# HydroController2016.net
KiCad netlist of a schematic drawn in Altium Designer
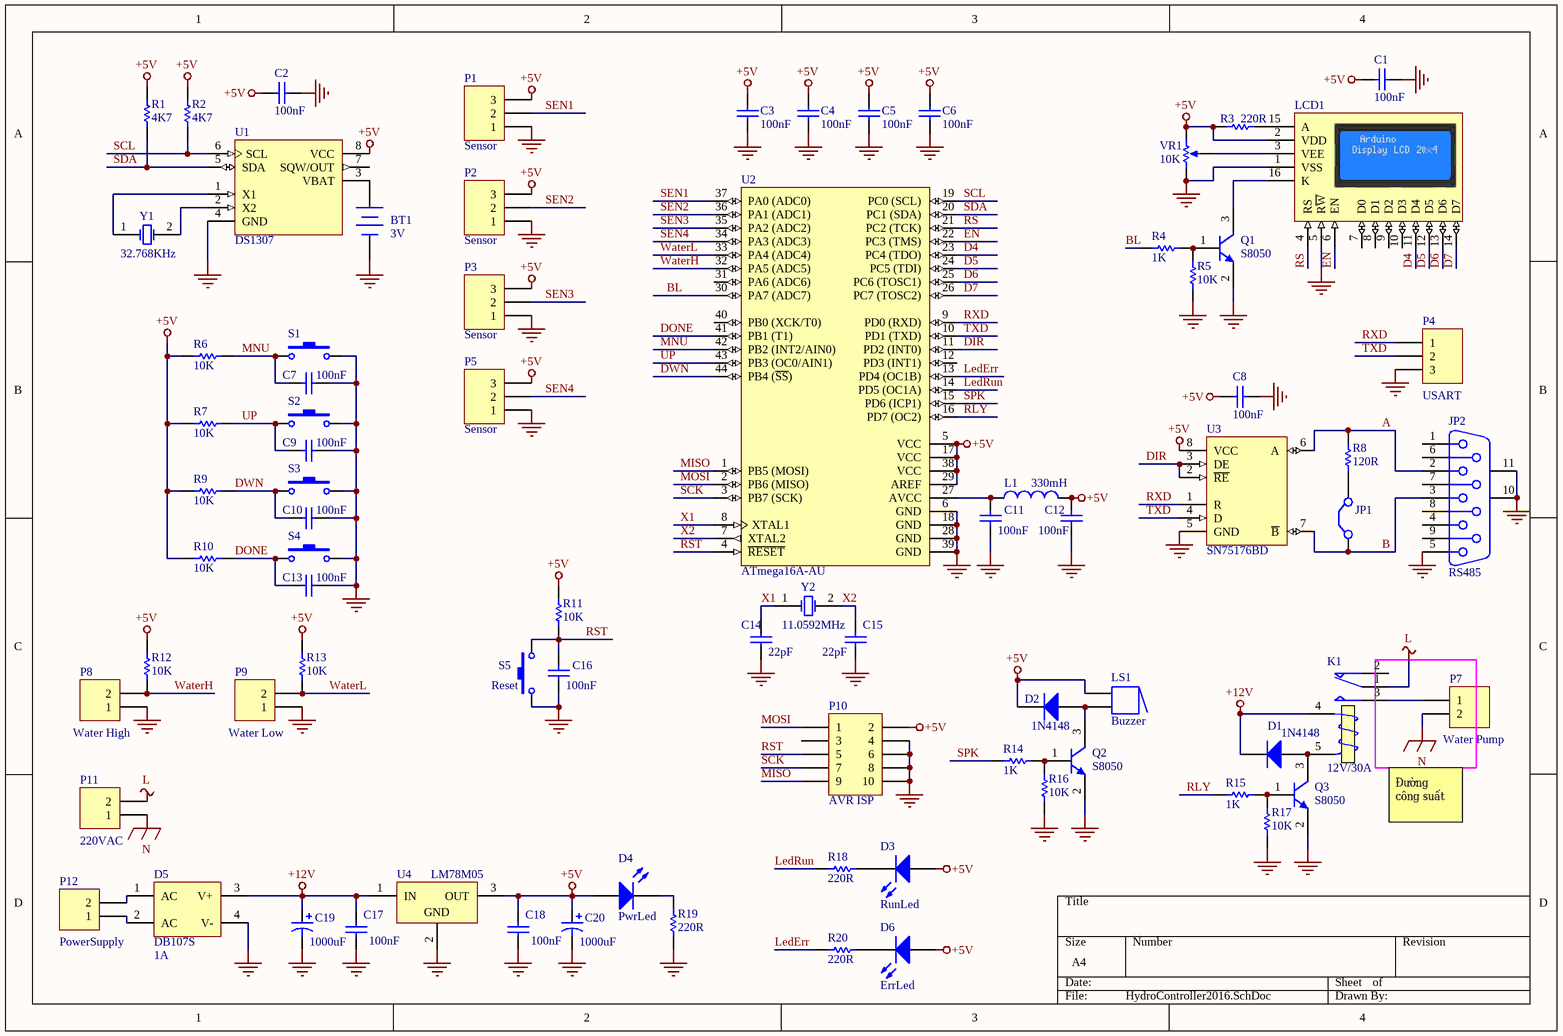
[diagram p0: HydroController2016.SchDoc]

(export (version "E")
  (design (tool "Eeschema 10.0.6"))
  (components
    (comp (ref "BT1")
      (value "3V")
      (footprint "SK-BATT-CR1220")
      (description "Multicell Battery")
      (libsource (lib "Miscellaneous Devices") (part "Battery"))
    )
    (comp (ref "C1")
      (value "100nF")
      (footprint "C-0805")
      (description "Capacitor")
      (fields (field (name "Comment") "104") (field (name "PUBLISHER") "Altium Limited"))
      (libsource (lib "Miscellaneous Devices") (part "Cap"))
    )
    (comp (ref "C2")
      (value "100nF")
      (footprint "C-0805")
      (description "Capacitor")
      (fields (field (name "Comment") "104") (field (name "PUBLISHER") "Altium Limited"))
      (libsource (lib "Miscellaneous Devices") (part "Cap"))
    )
    (comp (ref "C3")
      (value "100nF")
      (footprint "C-0805")
      (description "Capacitor")
      (fields (field (name "Comment") "104") (field (name "PUBLISHER") "Altium Limited"))
      (libsource (lib "Miscellaneous Devices") (part "Cap"))
    )
    (comp (ref "C4")
      (value "100nF")
      (footprint "C-0805")
      (description "Capacitor")
      (fields (field (name "Comment") "104") (field (name "PUBLISHER") "Altium Limited"))
      (libsource (lib "Miscellaneous Devices") (part "Cap"))
    )
    (comp (ref "C5")
      (value "100nF")
      (footprint "C-0805")
      (description "Capacitor")
      (fields (field (name "Comment") "104") (field (name "PUBLISHER") "Altium Limited"))
      (libsource (lib "Miscellaneous Devices") (part "Cap"))
    )
    (comp (ref "C6")
      (value "100nF")
      (footprint "C-0805")
      (description "Capacitor")
      (fields (field (name "Comment") "104") (field (name "PUBLISHER") "Altium Limited"))
      (libsource (lib "Miscellaneous Devices") (part "Cap"))
    )
    (comp (ref "C7")
      (value "100nF")
      (footprint "C-0805")
      (description "Capacitor")
      (fields (field (name "Comment") "104") (field (name "PUBLISHER") "Altium Limited"))
      (libsource (lib "Miscellaneous Devices") (part "Cap"))
    )
    (comp (ref "C8")
      (value "100nF")
      (footprint "C-0805")
      (description "Capacitor")
      (fields (field (name "Comment") "104") (field (name "PUBLISHER") "Altium Limited"))
      (libsource (lib "Miscellaneous Devices") (part "Cap"))
    )
    (comp (ref "C9")
      (value "100nF")
      (footprint "C-0805")
      (description "Capacitor")
      (fields (field (name "Comment") "104") (field (name "PUBLISHER") "Altium Limited"))
      (libsource (lib "Miscellaneous Devices") (part "Cap"))
    )
    (comp (ref "C10")
      (value "100nF")
      (footprint "C-0805")
      (description "Capacitor")
      (fields (field (name "Comment") "104") (field (name "PUBLISHER") "Altium Limited"))
      (libsource (lib "Miscellaneous Devices") (part "Cap"))
    )
    (comp (ref "C11")
      (value "100nF")
      (footprint "C-0805")
      (description "Capacitor")
      (fields (field (name "Comment") "104") (field (name "PUBLISHER") "Altium Limited"))
      (libsource (lib "Miscellaneous Devices") (part "Cap"))
    )
    (comp (ref "C12")
      (value "100nF")
      (footprint "C-0805")
      (description "Capacitor")
      (fields (field (name "Comment") "104") (field (name "PUBLISHER") "Altium Limited"))
      (libsource (lib "Miscellaneous Devices") (part "Cap"))
    )
    (comp (ref "C13")
      (value "100nF")
      (footprint "C-0805")
      (description "Capacitor")
      (fields (field (name "Comment") "104") (field (name "PUBLISHER") "Altium Limited"))
      (libsource (lib "Miscellaneous Devices") (part "Cap"))
    )
    (comp (ref "C14")
      (value "22pF")
      (footprint "C-0805")
      (description "Capacitor")
      (fields (field (name "Comment") "22") (field (name "PUBLISHER") "Altium Limited"))
      (libsource (lib "Miscellaneous Devices") (part "Cap"))
    )
    (comp (ref "C15")
      (value "22pF")
      (footprint "C-0805")
      (description "Capacitor")
      (fields (field (name "Comment") "22") (field (name "PUBLISHER") "Altium Limited"))
      (libsource (lib "Miscellaneous Devices") (part "Cap"))
    )
    (comp (ref "C16")
      (value "100nF")
      (footprint "C-0805")
      (description "Capacitor")
      (fields (field (name "Comment") "104") (field (name "PUBLISHER") "Altium Limited"))
      (libsource (lib "Miscellaneous Devices") (part "Cap"))
    )
    (comp (ref "C17")
      (value "100nF")
      (footprint "C-0805")
      (description "Capacitor")
      (fields (field (name "Comment") "104") (field (name "PUBLISHER") "Altium Limited"))
      (libsource (lib "Miscellaneous Devices") (part "Cap"))
    )
    (comp (ref "C18")
      (value "100nF")
      (footprint "C-0805")
      (description "Capacitor")
      (fields (field (name "Comment") "104") (field (name "PUBLISHER") "Altium Limited"))
      (libsource (lib "Miscellaneous Devices") (part "Cap"))
    )
    (comp (ref "C19")
      (value "1000uF")
      (footprint "C-ALU-10x10mm")
      (description "Tụ Tantalum 107E-100uF 25V SMD7343")
      (fields (field (name "Comment") "1000uF/25V") (field (name "PUBLISHER") "Altium Limited"))
      (libsource (lib "Miscellaneous Devices") (part "Cap Pol1"))
    )
    (comp (ref "C20")
      (value "1000uF")
      (footprint "C-ALU-10x10mm")
      (description "Tụ Tantalum 107E-100uF 25V SMD7343")
      (fields (field (name "Comment") "1000uF/25V") (field (name "PUBLISHER") "Altium Limited"))
      (libsource (lib "Miscellaneous Devices") (part "Cap Pol1"))
    )
    (comp (ref "D1")
      (value "1N4148")
      (footprint "D-SOD-80")
      (description "Default Diode")
      (libsource (lib "Miscellaneous Devices") (part "Diode"))
    )
    (comp (ref "D2")
      (value "1N4148")
      (footprint "D-SOD-80")
      (description "Default Diode")
      (libsource (lib "Miscellaneous Devices") (part "Diode"))
    )
    (comp (ref "D3")
      (value "RunLed")
      (footprint "LED-RECT-5x2mm")
      (description "Typical INFRARED GaAs LED")
      (fields (field (name "Comment") "LED-2x5-BLU"))
      (libsource (lib "Miscellaneous Devices") (part "LED0"))
    )
    (comp (ref "D4")
      (value "PwrLed")
      (footprint "LED-RECT-5x2mm")
      (description "Typical INFRARED GaAs LED")
      (fields (field (name "Comment") "LED-2x5-RED"))
      (libsource (lib "Miscellaneous Devices") (part "LED0"))
    )
    (comp (ref "D5")
      (value "DB107S")
      (footprint "D-DB-1A-SMD")
      (description "Diode Bridge")
      (fields (field (name "ALTIUM_VALUE") "1A"))
      (libsource (lib "Miscellaneous Devices") (part "Bridge2"))
    )
    (comp (ref "D6")
      (value "ErrLed")
      (footprint "LED-RECT-5x2mm")
      (description "Typical INFRARED GaAs LED")
      (fields (field (name "Comment") "LED-2x5-RED"))
      (libsource (lib "Miscellaneous Devices") (part "LED0"))
    )
    (comp (ref "JP1")
      (value "Jumper")
      (footprint "JP2.54-M-2-A")
      (description "Jumper Wire")
      (libsource (lib "Miscellaneous Devices") (part "Jumper"))
    )
    (comp (ref "JP2")
      (value "RS485")
      (footprint "CONN-DSUB9-MS")
      (description "Receptacle Assembly, 9 Position, Right Angle")
      (fields (field (name "Comment") "D Connector 9"))
      (libsource (lib "Miscellaneous Connectors") (part "D Connector 9"))
    )
    (comp (ref "K1")
      (value "12V/30A")
      (footprint "RL-5P-12V30A")
      (description "Single-Pole Dual-Throw Relay")
      (fields
        (field (name "MANUFACTURER") "Songle")
        (field (name "MANUFACTURER PART NUMBER") "SRD-12VDC-SL-C")
      )
      (libsource (lib "Miscellaneous Devices") (part "Relay"))
    )
    (comp (ref "L1")
      (value "330mH")
      (footprint "L-0805")
      (description "Inductor")
      (fields (field (name "PUBLISHER") "Altium Limited"))
      (libsource (lib "Miscellaneous Devices") (part "Inductor"))
    )
    (comp (ref "LCD1")
      (value "LCD2004")
      (footprint "LCD-2004")
      (description "Liquid Crystal Display")
      (libsource (lib "Dlib") (part "LCD2004"))
    )
    (comp (ref "LS1")
      (value "Buzzer")
      (footprint "Buzzer")
      (description "Magnetic Transducer Buzzer")
      (fields (field (name "PUBLISHER") "Altium Limited"))
      (libsource (lib "Miscellaneous Devices") (part "Buzzer"))
    )
    (comp (ref "P1")
      (value "Sensor")
      (footprint "CONN-XH2.54-3P")
      (description "Header, 3-Pin")
      (fields (field (name "Comment") "XH2.54-3P"))
      (libsource (lib "Miscellaneous Connectors") (part "Header 3"))
    )
    (comp (ref "P2")
      (value "Sensor")
      (footprint "CONN-XH2.54-3P")
      (description "Header, 3-Pin")
      (fields (field (name "Comment") "XH2.54-3P"))
      (libsource (lib "Miscellaneous Connectors") (part "Header 3"))
    )
    (comp (ref "P3")
      (value "Sensor")
      (footprint "CONN-XH2.54-3P")
      (description "Header, 3-Pin")
      (fields (field (name "Comment") "XH2.54-3P"))
      (libsource (lib "Miscellaneous Connectors") (part "Header 3"))
    )
    (comp (ref "P4")
      (value "USART")
      (footprint "CONN-XH2.54-3P")
      (description "Header, 3-Pin")
      (fields (field (name "Comment") "XH2.54-3P"))
      (libsource (lib "") (part "Header 3_1"))
    )
    (comp (ref "P5")
      (value "Sensor")
      (footprint "CONN-XH2.54-3P")
      (description "Header, 3-Pin")
      (fields (field (name "Comment") "XH2.54-3P"))
      (libsource (lib "Miscellaneous Connectors") (part "Header 3"))
    )
    (comp (ref "P7")
      (value "Water Pump")
      (footprint "TER-KF301-2")
      (description "Header, 2-Pin")
      (fields (field (name "Comment") "KF301-2P"))
      (libsource (lib "") (part "Header 2_1"))
    )
    (comp (ref "P8")
      (value "Water High")
      (footprint "CONN-XH2.54-2P")
      (description "Header, 2-Pin")
      (fields (field (name "Comment") "XH2.54-2P"))
      (libsource (lib "Miscellaneous Connectors") (part "Header 2"))
    )
    (comp (ref "P9")
      (value "Water Low")
      (footprint "CONN-XH2.54-2P")
      (description "Header, 2-Pin")
      (fields (field (name "Comment") "XH2.54-2P"))
      (libsource (lib "Miscellaneous Connectors") (part "Header 2"))
    )
    (comp (ref "P10")
      (value "AVR ISP")
      (footprint "CONN-IDC-5X2-A")
      (description "Header, 5-Pin, Dual row")
      (fields (field (name "Comment") "IDC5x2"))
      (libsource (lib "Miscellaneous Connectors") (part "Header 5X2"))
    )
    (comp (ref "P11")
      (value "220VAC")
      (footprint "TER-KF301-2")
      (description "Header, 2-Pin")
      (fields (field (name "Comment") "KF301-2P"))
      (libsource (lib "Miscellaneous Connectors") (part "Header 2"))
    )
    (comp (ref "P12")
      (value "PowerSupply")
      (footprint "TER-KF301-2")
      (description "Header, 2-Pin")
      (fields (field (name "Comment") "H2"))
      (libsource (lib "Miscellaneous Connectors") (part "Header 2"))
    )
    (comp (ref "Q1")
      (value "S8050")
      (footprint "SOT-23-3")
      (description "NPN Bipolar Transistor")
      (libsource (lib "Miscellaneous Devices") (part "NPN"))
    )
    (comp (ref "Q2")
      (value "S8050")
      (footprint "SOT-23-3")
      (description "NPN Bipolar Transistor")
      (libsource (lib "Miscellaneous Devices") (part "NPN"))
    )
    (comp (ref "Q3")
      (value "S8050")
      (footprint "SOT-23-3")
      (description "NPN Bipolar Transistor")
      (libsource (lib "Miscellaneous Devices") (part "NPN"))
    )
    (comp (ref "R1")
      (value "4K7")
      (footprint "R-0805")
      (description "Resistor")
      (fields (field (name "PUBLISHER") "Altium Limited"))
      (libsource (lib "Miscellaneous Devices") (part "Res1"))
    )
    (comp (ref "R2")
      (value "4K7")
      (footprint "R-0805")
      (description "Resistor")
      (fields (field (name "PUBLISHER") "Altium Limited"))
      (libsource (lib "Miscellaneous Devices") (part "Res1"))
    )
    (comp (ref "R3")
      (value "220R")
      (footprint "R-0805")
      (description "Resistor")
      (fields (field (name "PUBLISHER") "Altium Limited"))
      (libsource (lib "Miscellaneous Devices") (part "Res1"))
    )
    (comp (ref "R4")
      (value "1K")
      (footprint "R-0805")
      (description "Resistor")
      (fields (field (name "PUBLISHER") "Altium Limited"))
      (libsource (lib "Miscellaneous Devices") (part "Res1"))
    )
    (comp (ref "R5")
      (value "10K")
      (footprint "R-0805")
      (description "Resistor")
      (fields (field (name "PUBLISHER") "Altium Limited"))
      (libsource (lib "Miscellaneous Devices") (part "Res1"))
    )
    (comp (ref "R6")
      (value "10K")
      (footprint "R-0805")
      (description "Resistor")
      (fields (field (name "PUBLISHER") "Altium Limited"))
      (libsource (lib "Miscellaneous Devices") (part "Res1"))
    )
    (comp (ref "R7")
      (value "10K")
      (footprint "R-0805")
      (description "Resistor")
      (fields (field (name "PUBLISHER") "Altium Limited"))
      (libsource (lib "Miscellaneous Devices") (part "Res1"))
    )
    (comp (ref "R8")
      (value "120R")
      (footprint "R-0805")
      (description "Resistor")
      (fields (field (name "PUBLISHER") "Altium Limited"))
      (libsource (lib "Miscellaneous Devices") (part "Res1"))
    )
    (comp (ref "R9")
      (value "10K")
      (footprint "R-0805")
      (description "Resistor")
      (fields (field (name "PUBLISHER") "Altium Limited"))
      (libsource (lib "Miscellaneous Devices") (part "Res1"))
    )
    (comp (ref "R10")
      (value "10K")
      (footprint "R-0805")
      (description "Resistor")
      (fields (field (name "PUBLISHER") "Altium Limited"))
      (libsource (lib "Miscellaneous Devices") (part "Res1"))
    )
    (comp (ref "R11")
      (value "10K")
      (footprint "R-0805")
      (description "Resistor")
      (fields (field (name "PUBLISHER") "Altium Limited"))
      (libsource (lib "Miscellaneous Devices") (part "Res1"))
    )
    (comp (ref "R12")
      (value "10K")
      (footprint "R-0805")
      (description "Resistor")
      (fields (field (name "PUBLISHER") "Altium Limited"))
      (libsource (lib "Miscellaneous Devices") (part "Res1"))
    )
    (comp (ref "R13")
      (value "10K")
      (footprint "R-0805")
      (description "Resistor")
      (fields (field (name "PUBLISHER") "Altium Limited"))
      (libsource (lib "Miscellaneous Devices") (part "Res1"))
    )
    (comp (ref "R14")
      (value "1K")
      (footprint "R-0805")
      (description "Resistor")
      (fields (field (name "PUBLISHER") "Altium Limited"))
      (libsource (lib "Miscellaneous Devices") (part "Res1"))
    )
    (comp (ref "R15")
      (value "1K")
      (footprint "R-0805")
      (description "Resistor")
      (fields (field (name "PUBLISHER") "Altium Limited"))
      (libsource (lib "Miscellaneous Devices") (part "Res1"))
    )
    (comp (ref "R16")
      (value "10K")
      (footprint "R-0805")
      (description "Resistor")
      (fields (field (name "PUBLISHER") "Altium Limited"))
      (libsource (lib "Miscellaneous Devices") (part "Res1"))
    )
    (comp (ref "R17")
      (value "10K")
      (footprint "R-0805")
      (description "Resistor")
      (fields (field (name "PUBLISHER") "Altium Limited"))
      (libsource (lib "Miscellaneous Devices") (part "Res1"))
    )
    (comp (ref "R18")
      (value "220R")
      (footprint "R-0805")
      (description "Resistor")
      (fields (field (name "PUBLISHER") "Altium Limited"))
      (libsource (lib "Miscellaneous Devices") (part "Res1"))
    )
    (comp (ref "R19")
      (value "220R")
      (footprint "R-0805")
      (description "Resistor")
      (fields (field (name "PUBLISHER") "Altium Limited"))
      (libsource (lib "Miscellaneous Devices") (part "Res1"))
    )
    (comp (ref "R20")
      (value "220R")
      (footprint "R-0805")
      (description "Resistor")
      (fields (field (name "PUBLISHER") "Altium Limited"))
      (libsource (lib "Miscellaneous Devices") (part "Res1"))
    )
    (comp (ref "S1")
      (value "SW-T-S12")
      (footprint "SW-T-S12")
      (description "Switch")
      (libsource (lib "Miscellaneous Devices") (part "SW-PB"))
    )
    (comp (ref "S2")
      (value "SW-T-S12")
      (footprint "SW-T-S12")
      (description "Switch")
      (libsource (lib "Miscellaneous Devices") (part "SW-PB"))
    )
    (comp (ref "S3")
      (value "SW-T-S12")
      (footprint "SW-T-S12")
      (description "Switch")
      (libsource (lib "Miscellaneous Devices") (part "SW-PB"))
    )
    (comp (ref "S4")
      (value "SW-T-S12")
      (footprint "SW-T-S12")
      (description "Switch")
      (libsource (lib "Miscellaneous Devices") (part "SW-PB"))
    )
    (comp (ref "S5")
      (value "Reset")
      (footprint "SW-T-S6-SMD")
      (description "Switch")
      (fields (field (name "Comment") "SW-T-S6"))
      (libsource (lib "Miscellaneous Devices") (part "SW-PB"))
    )
    (comp (ref "U1")
      (value "DS1307")
      (footprint "SOIC-8")
      (description "64 X 8 Serial Real-Time Clock")
      (fields (field (name "PUBLISHER") "Altium Limited"))
      (libsource (lib "Dallas Peripheral Real Time Clock") (part "DS1307"))
    )
    (comp (ref "U2")
      (value "ATmega16A-AU")
      (footprint "TQFP-44")
      (fields (field (name "PUBLISHER") "Altium Limited"))
      (libsource (lib "Atmel Microcontroller 8-Bit megaAVR") (part "ATmega16A-AU"))
    )
    (comp (ref "U3")
      (value "SN75176BD")
      (footprint "SOIC-8")
      (description "Differential Bus Transceiver")
      (fields (field (name "PUBLISHER") "Altium Limited"))
      (libsource (lib "TI Interface Line Transceiver") (part "SN75176BD"))
    )
    (comp (ref "U4")
      (value "LM78M05")
      (footprint "TO-252-3")
      (description "3-Terminal Positive Voltage Regulators, 3-pin TO-252")
      (fields (field (name "MANUFACTURER") "Texas Instruments") (field (name "Comment") "LM78M05CDTX"))
      (libsource (lib "Altium Content Vault") (part "CMP-0062-00204-3"))
    )
    (comp (ref "VR1")
      (value "10K")
      (footprint "VR-RM063")
      (description "Potentiometer")
      (fields (field (name "PUBLISHER") "Altium Limited"))
      (libsource (lib "Miscellaneous Devices") (part "RPot"))
    )
    (comp (ref "Y1")
      (value "32.768KHz")
      (footprint "XTAL-AB38T-SMD")
      (description "Crystal Oscillator")
      (libsource (lib "Miscellaneous Devices") (part "XTAL"))
    )
    (comp (ref "Y2")
      (value "11.0592MHz")
      (footprint "XTAL-CSM7")
      (description "Crystal Oscillator")
      (libsource (lib "Miscellaneous Devices") (part "XTAL"))
    )
  )
  (nets
    (net (code "1") (name "+5V") (class "Default")
      (node (ref "C1") (pin "1") (pinfunction "1_1") (pintype "passive"))
      (node (ref "C12") (pin "2") (pinfunction "2_2") (pintype "passive"))
      (node (ref "C18") (pin "1") (pinfunction "1_1") (pintype "passive"))
      (node (ref "C2") (pin "2") (pinfunction "2_2") (pintype "passive"))
      (node (ref "C20") (pin "1") (pinfunction "1_1") (pintype "passive"))
      (node (ref "C3") (pin "2") (pinfunction "2_2") (pintype "passive"))
      (node (ref "C4") (pin "2") (pinfunction "2_2") (pintype "passive"))
      (node (ref "C5") (pin "2") (pinfunction "2_2") (pintype "passive"))
      (node (ref "C6") (pin "2") (pinfunction "2_2") (pintype "passive"))
      (node (ref "C8") (pin "2") (pinfunction "2_2") (pintype "passive"))
      (node (ref "D2") (pin "2") (pinfunction "K_2") (pintype "passive"))
      (node (ref "D3") (pin "1") (pinfunction "A_1") (pintype "passive"))
      (node (ref "D4") (pin "1") (pinfunction "A_1") (pintype "passive"))
      (node (ref "D6") (pin "1") (pinfunction "A_1") (pintype "passive"))
      (node (ref "L1") (pin "2") (pinfunction "2_2") (pintype "passive"))
      (node (ref "LCD1") (pin "2") (pinfunction "VDD_2") (pintype "power_in"))
      (node (ref "LS1") (pin "1") (pinfunction "1_1") (pintype "passive"))
      (node (ref "P1") (pin "3") (pinfunction "3_3") (pintype "passive"))
      (node (ref "P10") (pin "2") (pinfunction "2_2") (pintype "passive"))
      (node (ref "P2") (pin "3") (pinfunction "3_3") (pintype "passive"))
      (node (ref "P3") (pin "3") (pinfunction "3_3") (pintype "passive"))
      (node (ref "P5") (pin "3") (pinfunction "3_3") (pintype "passive"))
      (node (ref "R1") (pin "2") (pinfunction "2_2") (pintype "passive"))
      (node (ref "R10") (pin "2") (pinfunction "2_2") (pintype "passive"))
      (node (ref "R11") (pin "2") (pinfunction "2_2") (pintype "passive"))
      (node (ref "R12") (pin "2") (pinfunction "2_2") (pintype "passive"))
      (node (ref "R13") (pin "2") (pinfunction "2_2") (pintype "passive"))
      (node (ref "R2") (pin "2") (pinfunction "2_2") (pintype "passive"))
      (node (ref "R3") (pin "1") (pinfunction "1_1") (pintype "passive"))
      (node (ref "R6") (pin "2") (pinfunction "2_2") (pintype "passive"))
      (node (ref "R7") (pin "2") (pinfunction "2_2") (pintype "passive"))
      (node (ref "R9") (pin "2") (pinfunction "2_2") (pintype "passive"))
      (node (ref "U1") (pin "8") (pinfunction "VCC_8") (pintype "power_in"))
      (node (ref "U2") (pin "17") (pinfunction "VCC_17") (pintype "power_in"))
      (node (ref "U2") (pin "29") (pinfunction "AREF_29") (pintype "power_in"))
      (node (ref "U2") (pin "38") (pinfunction "VCC_38") (pintype "power_in"))
      (node (ref "U2") (pin "5") (pinfunction "VCC_5") (pintype "power_in"))
      (node (ref "U3") (pin "8") (pinfunction "VCC_8") (pintype "power_in"))
      (node (ref "U4") (pin "3") (pinfunction "OUT_3") (pintype "power_in"))
      (node (ref "VR1") (pin "3") (pinfunction "BOT_3") (pintype "passive"))
    )
    (net (code "2") (name "+12V") (class "Default")
      (node (ref "C17") (pin "1") (pinfunction "1_1") (pintype "passive"))
      (node (ref "C19") (pin "1") (pinfunction "1_1") (pintype "passive"))
      (node (ref "D1") (pin "2") (pinfunction "K_2") (pintype "passive"))
      (node (ref "D5") (pin "3") (pinfunction "V+_3") (pintype "passive"))
      (node (ref "K1") (pin "4") (pinfunction "T1_4") (pintype "passive"))
      (node (ref "U4") (pin "1") (pinfunction "IN_1") (pintype "power_in"))
    )
    (net (code "3") (name "/A") (class "Default")
      (node (ref "JP2") (pin "2") (pinfunction "2_2") (pintype "passive"))
      (node (ref "R8") (pin "1") (pinfunction "1_1") (pintype "passive"))
      (node (ref "U3") (pin "6") (pinfunction "A_6") (pintype "bidirectional"))
    )
    (net (code "4") (name "/B") (class "Default")
      (node (ref "JP1") (pin "1") (pinfunction "C1_1") (pintype "passive"))
      (node (ref "JP2") (pin "3") (pinfunction "3_3") (pintype "passive"))
      (node (ref "U3") (pin "7") (pinfunction "~{B}_7") (pintype "bidirectional"))
    )
    (net (code "5") (name "/BL") (class "Default")
      (node (ref "R4") (pin "2") (pinfunction "2_2") (pintype "passive"))
      (node (ref "U2") (pin "30") (pinfunction "PA7_(ADC7)_30") (pintype "bidirectional"))
    )
    (net (code "6") (name "/D4") (class "Default")
      (node (ref "LCD1") (pin "11") (pinfunction "D4_11") (pintype "bidirectional"))
      (node (ref "U2") (pin "23") (pinfunction "PC4_(TDO)_23") (pintype "bidirectional"))
    )
    (net (code "7") (name "/D5") (class "Default")
      (node (ref "LCD1") (pin "12") (pinfunction "D5_12") (pintype "bidirectional"))
      (node (ref "U2") (pin "24") (pinfunction "PC5_(TDI)_24") (pintype "bidirectional"))
    )
    (net (code "8") (name "/D6") (class "Default")
      (node (ref "LCD1") (pin "13") (pinfunction "D6_13") (pintype "bidirectional"))
      (node (ref "U2") (pin "25") (pinfunction "PC6_(TOSC1)_25") (pintype "bidirectional"))
    )
    (net (code "9") (name "/D7") (class "Default")
      (node (ref "LCD1") (pin "14") (pinfunction "D7_14") (pintype "bidirectional"))
      (node (ref "U2") (pin "26") (pinfunction "PC7_(TOSC2)_26") (pintype "bidirectional"))
    )
    (net (code "10") (name "/DIR") (class "Default")
      (node (ref "U2") (pin "11") (pinfunction "PD2_(INT0)_11") (pintype "bidirectional"))
      (node (ref "U3") (pin "2") (pinfunction "~{RE}_2") (pintype "input"))
      (node (ref "U3") (pin "3") (pinfunction "DE_3") (pintype "input"))
    )
    (net (code "11") (name "/DONE") (class "Default")
      (node (ref "C13") (pin "2") (pinfunction "2_2") (pintype "passive"))
      (node (ref "R10") (pin "1") (pinfunction "1_1") (pintype "passive"))
      (node (ref "S4") (pin "1") (pinfunction "1_1") (pintype "passive"))
      (node (ref "U2") (pin "41") (pinfunction "PB1_(T1)_41") (pintype "bidirectional"))
    )
    (net (code "12") (name "/DWN") (class "Default")
      (node (ref "C10") (pin "2") (pinfunction "2_2") (pintype "passive"))
      (node (ref "R9") (pin "1") (pinfunction "1_1") (pintype "passive"))
      (node (ref "S3") (pin "1") (pinfunction "1_1") (pintype "passive"))
      (node (ref "U2") (pin "44") (pinfunction "PB4_(~{SS})_44") (pintype "bidirectional"))
    )
    (net (code "13") (name "/EN") (class "Default")
      (node (ref "LCD1") (pin "6") (pinfunction "EN_6") (pintype "input"))
      (node (ref "U2") (pin "22") (pinfunction "PC3_(TMS)_22") (pintype "bidirectional"))
    )
    (net (code "14") (name "/LedErr") (class "Default")
      (node (ref "R20") (pin "1") (pinfunction "1_1") (pintype "passive"))
      (node (ref "U2") (pin "13") (pinfunction "PD4_(OC1B)_13") (pintype "bidirectional"))
    )
    (net (code "15") (name "/LedRun") (class "Default")
      (node (ref "R18") (pin "1") (pinfunction "1_1") (pintype "passive"))
      (node (ref "U2") (pin "14") (pinfunction "PD5_(OC1A)_14") (pintype "bidirectional"))
    )
    (net (code "16") (name "/MISO") (class "Default")
      (node (ref "P10") (pin "9") (pinfunction "9_9") (pintype "passive"))
      (node (ref "U2") (pin "1") (pinfunction "PB5_(MOSI)_1") (pintype "bidirectional"))
    )
    (net (code "17") (name "/MNU") (class "Default")
      (node (ref "C7") (pin "2") (pinfunction "2_2") (pintype "passive"))
      (node (ref "R6") (pin "1") (pinfunction "1_1") (pintype "passive"))
      (node (ref "S1") (pin "1") (pinfunction "1_1") (pintype "passive"))
      (node (ref "U2") (pin "42") (pinfunction "PB2_(INT2/AIN0)_42") (pintype "bidirectional"))
    )
    (net (code "18") (name "/MOSI") (class "Default")
      (node (ref "P10") (pin "1") (pinfunction "1_1") (pintype "passive"))
      (node (ref "U2") (pin "2") (pinfunction "PB6_(MISO)_2") (pintype "bidirectional"))
    )
    (net (code "19") (name "/RLY") (class "Default")
      (node (ref "R15") (pin "2") (pinfunction "2_2") (pintype "passive"))
      (node (ref "U2") (pin "16") (pinfunction "PD7_(OC2)_16") (pintype "bidirectional"))
    )
    (net (code "20") (name "/RS") (class "Default")
      (node (ref "LCD1") (pin "4") (pinfunction "RS_4") (pintype "input"))
      (node (ref "U2") (pin "21") (pinfunction "PC2_(TCK)_21") (pintype "bidirectional"))
    )
    (net (code "21") (name "/RST") (class "Default")
      (node (ref "C16") (pin "2") (pinfunction "2_2") (pintype "passive"))
      (node (ref "P10") (pin "5") (pinfunction "5_5") (pintype "passive"))
      (node (ref "R11") (pin "1") (pinfunction "1_1") (pintype "passive"))
      (node (ref "S5") (pin "2") (pinfunction "2_2") (pintype "passive"))
      (node (ref "U2") (pin "4") (pinfunction "~{RESET}_4") (pintype "input"))
    )
    (net (code "22") (name "/RXD") (class "Default")
      (node (ref "P4") (pin "1") (pinfunction "1_1") (pintype "passive"))
      (node (ref "U2") (pin "9") (pinfunction "PD0_(RXD)_9") (pintype "bidirectional"))
      (node (ref "U3") (pin "1") (pinfunction "R_1") (pintype "tri_state"))
    )
    (net (code "23") (name "/SCK") (class "Default")
      (node (ref "P10") (pin "7") (pinfunction "7_7") (pintype "passive"))
      (node (ref "U2") (pin "3") (pinfunction "PB7_(SCK)_3") (pintype "bidirectional"))
    )
    (net (code "24") (name "/SCL") (class "Default")
      (node (ref "R2") (pin "1") (pinfunction "1_1") (pintype "passive"))
      (node (ref "U1") (pin "6") (pinfunction "SCL_6") (pintype "input"))
      (node (ref "U2") (pin "19") (pinfunction "PC0_(SCL)_19") (pintype "bidirectional"))
    )
    (net (code "25") (name "/SDA") (class "Default")
      (node (ref "R1") (pin "1") (pinfunction "1_1") (pintype "passive"))
      (node (ref "U1") (pin "5") (pinfunction "SDA_5") (pintype "bidirectional"))
      (node (ref "U2") (pin "20") (pinfunction "PC1_(SDA)_20") (pintype "bidirectional"))
    )
    (net (code "26") (name "/SEN1") (class "Default")
      (node (ref "P1") (pin "2") (pinfunction "2_2") (pintype "passive"))
      (node (ref "U2") (pin "37") (pinfunction "PA0_(ADC0)_37") (pintype "bidirectional"))
    )
    (net (code "27") (name "/SEN2") (class "Default")
      (node (ref "P2") (pin "2") (pinfunction "2_2") (pintype "passive"))
      (node (ref "U2") (pin "36") (pinfunction "PA1_(ADC1)_36") (pintype "bidirectional"))
    )
    (net (code "28") (name "/SEN3") (class "Default")
      (node (ref "P3") (pin "2") (pinfunction "2_2") (pintype "passive"))
      (node (ref "U2") (pin "35") (pinfunction "PA2_(ADC2)_35") (pintype "bidirectional"))
    )
    (net (code "29") (name "/SEN4") (class "Default")
      (node (ref "P5") (pin "2") (pinfunction "2_2") (pintype "passive"))
      (node (ref "U2") (pin "34") (pinfunction "PA3_(ADC3)_34") (pintype "bidirectional"))
    )
    (net (code "30") (name "/SPK") (class "Default")
      (node (ref "R14") (pin "2") (pinfunction "2_2") (pintype "passive"))
      (node (ref "U2") (pin "15") (pinfunction "PD6_(ICP1)_15") (pintype "bidirectional"))
    )
    (net (code "31") (name "/TXD") (class "Default")
      (node (ref "P4") (pin "2") (pinfunction "2_2") (pintype "passive"))
      (node (ref "U2") (pin "10") (pinfunction "PD1_(TXD)_10") (pintype "bidirectional"))
      (node (ref "U3") (pin "4") (pinfunction "D_4") (pintype "input"))
    )
    (net (code "32") (name "/UP") (class "Default")
      (node (ref "C9") (pin "2") (pinfunction "2_2") (pintype "passive"))
      (node (ref "R7") (pin "1") (pinfunction "1_1") (pintype "passive"))
      (node (ref "S2") (pin "1") (pinfunction "1_1") (pintype "passive"))
      (node (ref "U2") (pin "43") (pinfunction "PB3_(OC0/AIN1)_43") (pintype "bidirectional"))
    )
    (net (code "33") (name "/WaterH") (class "Default")
      (node (ref "P8") (pin "2") (pinfunction "2_2") (pintype "passive"))
      (node (ref "R12") (pin "1") (pinfunction "1_1") (pintype "passive"))
      (node (ref "U2") (pin "32") (pinfunction "PA5_(ADC5)_32") (pintype "bidirectional"))
    )
    (net (code "34") (name "/WaterL") (class "Default")
      (node (ref "P9") (pin "2") (pinfunction "2_2") (pintype "passive"))
      (node (ref "R13") (pin "1") (pinfunction "1_1") (pintype "passive"))
      (node (ref "U2") (pin "33") (pinfunction "PA4_(ADC4)_33") (pintype "bidirectional"))
    )
    (net (code "35") (name "/X1") (class "Default")
      (node (ref "C14") (pin "2") (pinfunction "2_2") (pintype "passive"))
      (node (ref "U2") (pin "8") (pinfunction "XTAL1_8") (pintype "input"))
      (node (ref "Y2") (pin "1") (pinfunction "OSC1_1") (pintype "passive"))
    )
    (net (code "36") (name "/X2") (class "Default")
      (node (ref "C15") (pin "2") (pinfunction "2_2") (pintype "passive"))
      (node (ref "U2") (pin "7") (pinfunction "XTAL2_7") (pintype "output"))
      (node (ref "Y2") (pin "2") (pinfunction "OSC2_2") (pintype "passive"))
    )
    (net (code "37") (name "GND") (class "Default")
      (node (ref "BT1") (pin "2") (pinfunction "-_2") (pintype "passive"))
      (node (ref "C1") (pin "2") (pinfunction "2_2") (pintype "passive"))
      (node (ref "C10") (pin "1") (pinfunction "1_1") (pintype "passive"))
      (node (ref "C11") (pin "1") (pinfunction "1_1") (pintype "passive"))
      (node (ref "C12") (pin "1") (pinfunction "1_1") (pintype "passive"))
      (node (ref "C13") (pin "1") (pinfunction "1_1") (pintype "passive"))
      (node (ref "C14") (pin "1") (pinfunction "1_1") (pintype "passive"))
      (node (ref "C15") (pin "1") (pinfunction "1_1") (pintype "passive"))
      (node (ref "C16") (pin "1") (pinfunction "1_1") (pintype "passive"))
      (node (ref "C17") (pin "2") (pinfunction "2_2") (pintype "passive"))
      (node (ref "C18") (pin "2") (pinfunction "2_2") (pintype "passive"))
      (node (ref "C19") (pin "2") (pinfunction "2_2") (pintype "passive"))
      (node (ref "C2") (pin "1") (pinfunction "1_1") (pintype "passive"))
      (node (ref "C20") (pin "2") (pinfunction "2_2") (pintype "passive"))
      (node (ref "C3") (pin "1") (pinfunction "1_1") (pintype "passive"))
      (node (ref "C4") (pin "1") (pinfunction "1_1") (pintype "passive"))
      (node (ref "C5") (pin "1") (pinfunction "1_1") (pintype "passive"))
      (node (ref "C6") (pin "1") (pinfunction "1_1") (pintype "passive"))
      (node (ref "C7") (pin "1") (pinfunction "1_1") (pintype "passive"))
      (node (ref "C8") (pin "1") (pinfunction "1_1") (pintype "passive"))
      (node (ref "C9") (pin "1") (pinfunction "1_1") (pintype "passive"))
      (node (ref "D5") (pin "4") (pinfunction "V-_4") (pintype "passive"))
      (node (ref "JP2") (pin "10") (pinfunction "MH1_10") (pintype "passive"))
      (node (ref "JP2") (pin "11") (pinfunction "MH2_11") (pintype "passive"))
      (node (ref "JP2") (pin "5") (pinfunction "5_5") (pintype "passive"))
      (node (ref "LCD1") (pin "1") (pinfunction "VSS_1") (pintype "power_in"))
      (node (ref "LCD1") (pin "5") (pinfunction "R~{W}_5") (pintype "input"))
      (node (ref "P1") (pin "1") (pinfunction "1_1") (pintype "passive"))
      (node (ref "P10") (pin "10") (pinfunction "10_10") (pintype "passive"))
      (node (ref "P10") (pin "4") (pinfunction "4_4") (pintype "passive"))
      (node (ref "P10") (pin "6") (pinfunction "6_6") (pintype "passive"))
      (node (ref "P10") (pin "8") (pinfunction "8_8") (pintype "passive"))
      (node (ref "P2") (pin "1") (pinfunction "1_1") (pintype "passive"))
      (node (ref "P3") (pin "1") (pinfunction "1_1") (pintype "passive"))
      (node (ref "P4") (pin "3") (pinfunction "3_3") (pintype "passive"))
      (node (ref "P5") (pin "1") (pinfunction "1_1") (pintype "passive"))
      (node (ref "P8") (pin "1") (pinfunction "1_1") (pintype "passive"))
      (node (ref "P9") (pin "1") (pinfunction "1_1") (pintype "passive"))
      (node (ref "Q1") (pin "2") (pinfunction "E_2") (pintype "passive"))
      (node (ref "Q2") (pin "2") (pinfunction "E_2") (pintype "passive"))
      (node (ref "Q3") (pin "2") (pinfunction "E_2") (pintype "passive"))
      (node (ref "R16") (pin "1") (pinfunction "1_1") (pintype "passive"))
      (node (ref "R17") (pin "1") (pinfunction "1_1") (pintype "passive"))
      (node (ref "R19") (pin "1") (pinfunction "1_1") (pintype "passive"))
      (node (ref "R5") (pin "1") (pinfunction "1_1") (pintype "passive"))
      (node (ref "S1") (pin "2") (pinfunction "2_2") (pintype "passive"))
      (node (ref "S2") (pin "2") (pinfunction "2_2") (pintype "passive"))
      (node (ref "S3") (pin "2") (pinfunction "2_2") (pintype "passive"))
      (node (ref "S4") (pin "2") (pinfunction "2_2") (pintype "passive"))
      (node (ref "S5") (pin "1") (pinfunction "1_1") (pintype "passive"))
      (node (ref "U1") (pin "4") (pinfunction "GND_4") (pintype "power_in"))
      (node (ref "U2") (pin "18") (pinfunction "GND_18") (pintype "power_in"))
      (node (ref "U2") (pin "28") (pinfunction "GND_28") (pintype "power_in"))
      (node (ref "U2") (pin "39") (pinfunction "GND_39") (pintype "power_in"))
      (node (ref "U2") (pin "6") (pinfunction "GND_6") (pintype "power_in"))
      (node (ref "U3") (pin "5") (pinfunction "GND_5") (pintype "power_in"))
      (node (ref "U4") (pin "2") (pinfunction "GND_2") (pintype "power_in"))
      (node (ref "VR1") (pin "1") (pinfunction "TOP_1") (pintype "passive"))
    )
    (net (code "38") (name "L") (class "Default")
      (node (ref "K1") (pin "1") (pinfunction "COM_1") (pintype "passive"))
      (node (ref "P11") (pin "2") (pinfunction "2_2") (pintype "passive"))
    )
    (net (code "39") (name "N") (class "Default")
      (node (ref "P11") (pin "1") (pinfunction "1_1") (pintype "passive"))
      (node (ref "P7") (pin "2") (pinfunction "2_2") (pintype "passive"))
    )
    (net (code "40") (name "Net-(BT1-+)") (class "Default")
      (node (ref "BT1") (pin "1") (pinfunction "+_1") (pintype "passive"))
      (node (ref "U1") (pin "3") (pinfunction "VBAT_3") (pintype "power_in"))
    )
    (net (code "41") (name "Net-(D1-A)") (class "Default")
      (node (ref "D1") (pin "1") (pinfunction "A_1") (pintype "passive"))
      (node (ref "K1") (pin "5") (pinfunction "T2_5") (pintype "passive"))
      (node (ref "Q3") (pin "3") (pinfunction "C_3") (pintype "passive"))
    )
    (net (code "42") (name "Net-(D2-A)") (class "Default")
      (node (ref "D2") (pin "1") (pinfunction "A_1") (pintype "passive"))
      (node (ref "LS1") (pin "2") (pinfunction "2_2") (pintype "passive"))
      (node (ref "Q2") (pin "3") (pinfunction "C_3") (pintype "passive"))
    )
    (net (code "43") (name "Net-(D3-K)") (class "Default")
      (node (ref "D3") (pin "2") (pinfunction "K_2") (pintype "passive"))
      (node (ref "R18") (pin "2") (pinfunction "2_2") (pintype "passive"))
    )
    (net (code "44") (name "Net-(D4-K)") (class "Default")
      (node (ref "D4") (pin "2") (pinfunction "K_2") (pintype "passive"))
      (node (ref "R19") (pin "2") (pinfunction "2_2") (pintype "passive"))
    )
    (net (code "45") (name "Net-(D5-AC-Pad1)") (class "Default")
      (node (ref "D5") (pin "1") (pinfunction "AC_1") (pintype "passive"))
      (node (ref "P12") (pin "2") (pinfunction "2_2") (pintype "passive"))
    )
    (net (code "46") (name "Net-(D5-AC-Pad2)") (class "Default")
      (node (ref "D5") (pin "2") (pinfunction "AC_2") (pintype "passive"))
      (node (ref "P12") (pin "1") (pinfunction "1_1") (pintype "passive"))
    )
    (net (code "47") (name "Net-(D6-K)") (class "Default")
      (node (ref "D6") (pin "2") (pinfunction "K_2") (pintype "passive"))
      (node (ref "R20") (pin "2") (pinfunction "2_2") (pintype "passive"))
    )
    (net (code "48") (name "Net-(JP1-C2)") (class "Default")
      (node (ref "JP1") (pin "2") (pinfunction "C2_2") (pintype "passive"))
      (node (ref "R8") (pin "2") (pinfunction "2_2") (pintype "passive"))
    )
    (net (code "49") (name "Net-(K1-NO)") (class "Default")
      (node (ref "K1") (pin "3") (pinfunction "NO_3") (pintype "passive"))
      (node (ref "P7") (pin "1") (pinfunction "1_1") (pintype "passive"))
    )
    (net (code "50") (name "Net-(LCD1-A)") (class "Default")
      (node (ref "LCD1") (pin "15") (pinfunction "A_15") (pintype "power_in"))
      (node (ref "R3") (pin "2") (pinfunction "2_2") (pintype "passive"))
    )
    (net (code "51") (name "Net-(LCD1-K)") (class "Default")
      (node (ref "LCD1") (pin "16") (pinfunction "K_16") (pintype "power_in"))
      (node (ref "Q1") (pin "3") (pinfunction "C_3") (pintype "passive"))
    )
    (net (code "52") (name "Net-(LCD1-VEE)") (class "Default")
      (node (ref "LCD1") (pin "3") (pinfunction "VEE_3") (pintype "power_in"))
      (node (ref "VR1") (pin "2") (pinfunction "TAP_2") (pintype "passive"))
    )
    (net (code "53") (name "Net-(Q1-B)") (class "Default")
      (node (ref "Q1") (pin "1") (pinfunction "B_1") (pintype "passive"))
      (node (ref "R4") (pin "1") (pinfunction "1_1") (pintype "passive"))
      (node (ref "R5") (pin "2") (pinfunction "2_2") (pintype "passive"))
    )
    (net (code "54") (name "Net-(Q2-B)") (class "Default")
      (node (ref "Q2") (pin "1") (pinfunction "B_1") (pintype "passive"))
      (node (ref "R14") (pin "1") (pinfunction "1_1") (pintype "passive"))
      (node (ref "R16") (pin "2") (pinfunction "2_2") (pintype "passive"))
    )
    (net (code "55") (name "Net-(Q3-B)") (class "Default")
      (node (ref "Q3") (pin "1") (pinfunction "B_1") (pintype "passive"))
      (node (ref "R15") (pin "1") (pinfunction "1_1") (pintype "passive"))
      (node (ref "R17") (pin "2") (pinfunction "2_2") (pintype "passive"))
    )
    (net (code "56") (name "Net-(U1-X1)") (class "Default")
      (node (ref "U1") (pin "1") (pinfunction "X1_1") (pintype "input"))
      (node (ref "Y1") (pin "1") (pinfunction "OSC1_1") (pintype "passive"))
    )
    (net (code "57") (name "Net-(U1-X2)") (class "Default")
      (node (ref "U1") (pin "2") (pinfunction "X2_2") (pintype "input"))
      (node (ref "Y1") (pin "2") (pinfunction "OSC2_2") (pintype "passive"))
    )
    (net (code "58") (name "Net-(U2-AVCC)") (class "Default")
      (node (ref "C11") (pin "2") (pinfunction "2_2") (pintype "passive"))
      (node (ref "L1") (pin "1") (pinfunction "1_1") (pintype "passive"))
      (node (ref "U2") (pin "27") (pinfunction "AVCC_27") (pintype "power_in"))
    )
    (net (code "59") (name "unconnected-(JP2-Pad1)") (class "Default")
      (node (ref "JP2") (pin "1") (pinfunction "1_1") (pintype "passive"))
    )
    (net (code "60") (name "unconnected-(JP2-Pad4)") (class "Default")
      (node (ref "JP2") (pin "4") (pinfunction "4_4") (pintype "passive"))
    )
    (net (code "61") (name "unconnected-(JP2-Pad6)") (class "Default")
      (node (ref "JP2") (pin "6") (pinfunction "6_6") (pintype "passive"))
    )
    (net (code "62") (name "unconnected-(JP2-Pad7)") (class "Default")
      (node (ref "JP2") (pin "7") (pinfunction "7_7") (pintype "passive"))
    )
    (net (code "63") (name "unconnected-(JP2-Pad8)") (class "Default")
      (node (ref "JP2") (pin "8") (pinfunction "8_8") (pintype "passive"))
    )
    (net (code "64") (name "unconnected-(JP2-Pad9)") (class "Default")
      (node (ref "JP2") (pin "9") (pinfunction "9_9") (pintype "passive"))
    )
    (net (code "65") (name "unconnected-(K1-NC-Pad2)") (class "Default")
      (node (ref "K1") (pin "2") (pinfunction "NC_2") (pintype "passive"))
    )
    (net (code "66") (name "unconnected-(LCD1-D0-Pad7)") (class "Default")
      (node (ref "LCD1") (pin "7") (pinfunction "D0_7") (pintype "bidirectional"))
    )
    (net (code "67") (name "unconnected-(LCD1-D1-Pad8)") (class "Default")
      (node (ref "LCD1") (pin "8") (pinfunction "D1_8") (pintype "bidirectional"))
    )
    (net (code "68") (name "unconnected-(LCD1-D2-Pad9)") (class "Default")
      (node (ref "LCD1") (pin "9") (pinfunction "D2_9") (pintype "bidirectional"))
    )
    (net (code "69") (name "unconnected-(LCD1-D3-Pad10)") (class "Default")
      (node (ref "LCD1") (pin "10") (pinfunction "D3_10") (pintype "bidirectional"))
    )
    (net (code "70") (name "unconnected-(P10-Pad3)") (class "Default")
      (node (ref "P10") (pin "3") (pinfunction "3_3") (pintype "passive"))
    )
    (net (code "71") (name "unconnected-(U1-SQW{slash}OUT-Pad7)") (class "Default")
      (node (ref "U1") (pin "7") (pinfunction "SQW/OUT_7") (pintype "output"))
    )
    (net (code "72") (name "unconnected-(U2-PA6_(ADC6)-Pad31)") (class "Default")
      (node (ref "U2") (pin "31") (pinfunction "PA6_(ADC6)_31") (pintype "bidirectional"))
    )
    (net (code "73") (name "unconnected-(U2-PB0_(XCK{slash}T0)-Pad40)") (class "Default")
      (node (ref "U2") (pin "40") (pinfunction "PB0_(XCK/T0)_40") (pintype "bidirectional"))
    )
    (net (code "74") (name "unconnected-(U2-PD3_(INT1)-Pad12)") (class "Default")
      (node (ref "U2") (pin "12") (pinfunction "PD3_(INT1)_12") (pintype "bidirectional"))
    )
  )
)
